# Floor_u_controller.net
KiCad netlist of a schematic drawn in Altium Designer
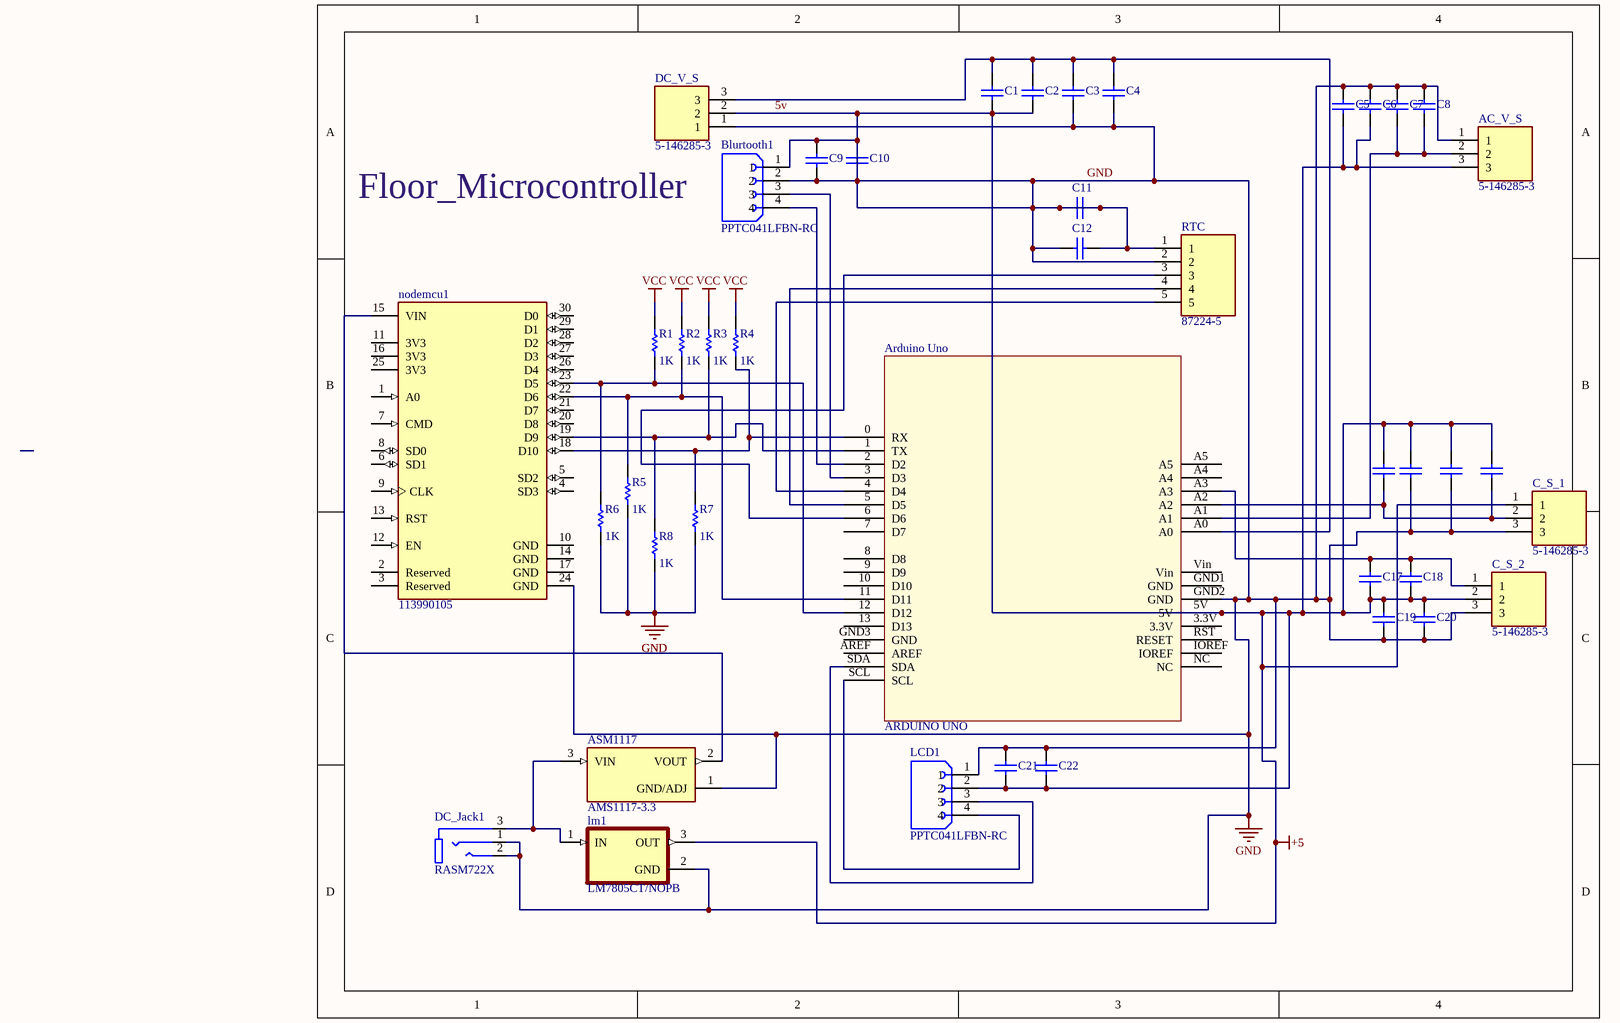
[diagram p0: Floor_u_controller.SchDoc]

(export (version "E")
  (design (tool "Eeschema 10.0.6"))
  (components
    (comp (ref "AC_V_S")
      (value "5-146285-3")
      (footprint "TE_5-146285-3:TE_5-146285-3")
      (libsource (lib "") (part "5-146285-3_1"))
    )
    (comp (ref "Arduino Uno")
      (value "ARDUINO UNO")
      (footprint "ARDUINO UNO")
      (libsource (lib "Arduino") (part "ARDUINO UNO"))
    )
    (comp (ref "ASM1117")
      (value "AMS1117-3.3")
      (footprint "SOT229P700X180-4N")
      (description "Sot223/Pkg 1-Amp 3.3-Volt Low Drop Out Voltage Regulatator")
      (fields (field (name "MF") "Advanced Monolithic Systems"))
      (libsource (lib "AMS1117-3.3") (part "AMS1117-3.3"))
    )
    (comp (ref "Blurtooth1")
      (value "PPTC041LFBN-RC")
      (footprint "SULLINS_PPTC041LFBN-RC")
      (description "4 Position Header Connector 0.100 (2.54mm) Through Hole Tin")
      (fields (field (name "MF") "Sullins Connector") (field (name "DIGI-KEY_PART_NUMBER") "S7002-ND"))
      (libsource (lib "PPTC041LFBN-RC") (part "PPTC041LFBN-RC"))
    )
    (comp (ref "C1")
      (value "~")
      (footprint "0805")
      (description "Capacitor")
      (fields (field (name "PUBLISHER") "Altium Limited"))
      (libsource (lib "Miscellaneous Devices") (part "Cap"))
    )
    (comp (ref "C2")
      (value "~")
      (footprint "0805")
      (description "Capacitor")
      (fields (field (name "PUBLISHER") "Altium Limited"))
      (libsource (lib "Miscellaneous Devices") (part "Cap"))
    )
    (comp (ref "C3")
      (value "~")
      (footprint "0805")
      (description "Capacitor")
      (fields (field (name "PUBLISHER") "Altium Limited"))
      (libsource (lib "Miscellaneous Devices") (part "Cap"))
    )
    (comp (ref "C4")
      (value "~")
      (footprint "0805")
      (description "Capacitor")
      (fields (field (name "PUBLISHER") "Altium Limited"))
      (libsource (lib "Miscellaneous Devices") (part "Cap"))
    )
    (comp (ref "C5")
      (value "~")
      (footprint "0805")
      (description "Capacitor")
      (fields (field (name "PUBLISHER") "Altium Limited"))
      (libsource (lib "Miscellaneous Devices") (part "Cap"))
    )
    (comp (ref "C6")
      (value "~")
      (footprint "0805")
      (description "Capacitor")
      (fields (field (name "PUBLISHER") "Altium Limited"))
      (libsource (lib "Miscellaneous Devices") (part "Cap"))
    )
    (comp (ref "C7")
      (value "~")
      (footprint "0805")
      (description "Capacitor")
      (fields (field (name "PUBLISHER") "Altium Limited"))
      (libsource (lib "Miscellaneous Devices") (part "Cap"))
    )
    (comp (ref "C8")
      (value "~")
      (footprint "0805")
      (description "Capacitor")
      (fields (field (name "PUBLISHER") "Altium Limited"))
      (libsource (lib "Miscellaneous Devices") (part "Cap"))
    )
    (comp (ref "C9")
      (value "~")
      (footprint "0805")
      (description "Capacitor")
      (fields (field (name "PUBLISHER") "Altium Limited"))
      (libsource (lib "Miscellaneous Devices") (part "Cap"))
    )
    (comp (ref "C10")
      (value "~")
      (footprint "0805")
      (description "Capacitor")
      (fields (field (name "PUBLISHER") "Altium Limited"))
      (libsource (lib "Miscellaneous Devices") (part "Cap"))
    )
    (comp (ref "C11")
      (value "~")
      (footprint "0805")
      (description "Capacitor")
      (fields (field (name "PUBLISHER") "Altium Limited"))
      (libsource (lib "Miscellaneous Devices") (part "Cap"))
    )
    (comp (ref "C12")
      (value "~")
      (footprint "0805")
      (description "Capacitor")
      (fields (field (name "PUBLISHER") "Altium Limited"))
      (libsource (lib "Miscellaneous Devices") (part "Cap"))
    )
    (comp (ref "C13")
      (value "~")
      (footprint "0805")
      (description "Capacitor")
      (fields (field (name "PUBLISHER") "Altium Limited"))
      (libsource (lib "Miscellaneous Devices") (part "Cap"))
    )
    (comp (ref "C14")
      (value "~")
      (footprint "0805")
      (description "Capacitor")
      (fields (field (name "PUBLISHER") "Altium Limited"))
      (libsource (lib "Miscellaneous Devices") (part "Cap"))
    )
    (comp (ref "C15")
      (value "~")
      (footprint "0805")
      (description "Capacitor")
      (fields (field (name "PUBLISHER") "Altium Limited"))
      (libsource (lib "Miscellaneous Devices") (part "Cap"))
    )
    (comp (ref "C16")
      (value "~")
      (footprint "0805")
      (description "Capacitor")
      (fields (field (name "PUBLISHER") "Altium Limited"))
      (libsource (lib "Miscellaneous Devices") (part "Cap"))
    )
    (comp (ref "C17")
      (value "~")
      (footprint "0805")
      (description "Capacitor")
      (fields (field (name "PUBLISHER") "Altium Limited"))
      (libsource (lib "Miscellaneous Devices") (part "Cap"))
    )
    (comp (ref "C18")
      (value "~")
      (footprint "0805")
      (description "Capacitor")
      (fields (field (name "PUBLISHER") "Altium Limited"))
      (libsource (lib "Miscellaneous Devices") (part "Cap"))
    )
    (comp (ref "C19")
      (value "~")
      (footprint "0805")
      (description "Capacitor")
      (fields (field (name "PUBLISHER") "Altium Limited"))
      (libsource (lib "Miscellaneous Devices") (part "Cap"))
    )
    (comp (ref "C20")
      (value "~")
      (footprint "0805")
      (description "Capacitor")
      (fields (field (name "PUBLISHER") "Altium Limited"))
      (libsource (lib "Miscellaneous Devices") (part "Cap"))
    )
    (comp (ref "C21")
      (value "~")
      (footprint "0805")
      (description "Capacitor")
      (fields (field (name "PUBLISHER") "Altium Limited"))
      (libsource (lib "Miscellaneous Devices") (part "Cap"))
    )
    (comp (ref "C22")
      (value "~")
      (footprint "0805")
      (description "Capacitor")
      (fields (field (name "PUBLISHER") "Altium Limited"))
      (libsource (lib "Miscellaneous Devices") (part "Cap"))
    )
    (comp (ref "C_S_1")
      (value "5-146285-3")
      (footprint "TE_5-146285-3:TE_5-146285-3")
      (libsource (lib "") (part "5-146285-3_1"))
    )
    (comp (ref "C_S_2")
      (value "5-146285-3")
      (footprint "TE_5-146285-3:TE_5-146285-3")
      (libsource (lib "") (part "5-146285-3_1"))
    )
    (comp (ref "DC_Jack1")
      (value "RASM722X")
      (footprint "SWITCHCRAFT_RASM722X")
      (fields (field (name "MF") "Switchcraft"))
      (libsource (lib "RASM722X") (part "RASM722X"))
    )
    (comp (ref "DC_V_S")
      (value "5-146285-3")
      (footprint "TE_5-146285-3:TE_5-146285-3")
      (libsource (lib "5-146285-3") (part "5-146285-3"))
    )
    (comp (ref "LCD1")
      (value "PPTC041LFBN-RC")
      (footprint "SULLINS_PPTC041LFBN-RC")
      (description "4 Position Header Connector 0.100 (2.54mm) Through Hole Tin")
      (fields (field (name "MF") "Sullins Connector") (field (name "DIGI-KEY_PART_NUMBER") "S7002-ND"))
      (libsource (lib "PPTC041LFBN-RC") (part "PPTC041LFBN-RC"))
    )
    (comp (ref "lm1")
      (value "LM7805CT/NOPB")
      (footprint "TO254P1054X470X2600-3")
      (description "Linear Voltage Regulator IC Positive Fixed 1 Output 1.5A TO-220-3")
      (fields (field (name "MF") "ON Semiconductor") (field (name "MP") "LM7805CT"))
      (libsource (lib "LM7805CT_NOPB") (part "LM7805CT/NOPB"))
    )
    (comp (ref "nodemcu1")
      (value "113990105")
      (footprint "FP-113990105-MFG")
      (description "NODEMCU V2 LUA BASED ESP8266 DEV")
      (libsource (lib "nodemcu") (part "CMP-138991-000001-1"))
    )
    (comp (ref "R1")
      (value "1K")
      (footprint "0805")
      (description "Resistor")
      (fields (field (name "PUBLISHER") "Altium Limited"))
      (libsource (lib "Miscellaneous Devices") (part "Res1"))
    )
    (comp (ref "R2")
      (value "1K")
      (footprint "0805")
      (description "Resistor")
      (fields (field (name "PUBLISHER") "Altium Limited"))
      (libsource (lib "Miscellaneous Devices") (part "Res1"))
    )
    (comp (ref "R3")
      (value "1K")
      (footprint "0805")
      (description "Resistor")
      (fields (field (name "PUBLISHER") "Altium Limited"))
      (libsource (lib "Miscellaneous Devices") (part "Res1"))
    )
    (comp (ref "R4")
      (value "1K")
      (footprint "0805")
      (description "Resistor")
      (fields (field (name "PUBLISHER") "Altium Limited"))
      (libsource (lib "Miscellaneous Devices") (part "Res1"))
    )
    (comp (ref "R5")
      (value "1K")
      (footprint "0805")
      (description "Resistor")
      (fields (field (name "PUBLISHER") "Altium Limited"))
      (libsource (lib "Miscellaneous Devices") (part "Res1"))
    )
    (comp (ref "R6")
      (value "1K")
      (footprint "0805")
      (description "Resistor")
      (fields (field (name "PUBLISHER") "Altium Limited"))
      (libsource (lib "Miscellaneous Devices") (part "Res1"))
    )
    (comp (ref "R7")
      (value "1K")
      (footprint "0805")
      (description "Resistor")
      (fields (field (name "PUBLISHER") "Altium Limited"))
      (libsource (lib "Miscellaneous Devices") (part "Res1"))
    )
    (comp (ref "R8")
      (value "1K")
      (footprint "0805")
      (description "Resistor")
      (fields (field (name "PUBLISHER") "Altium Limited"))
      (libsource (lib "Miscellaneous Devices") (part "Res1"))
    )
    (comp (ref "RTC")
      (value "87224-5")
      (footprint "TE_87224-5:TE_87224-5")
      (description "Conn Unshrouded Header HDR 5 POS 2.54mm Solder ST Thru-Hole")
      (fields (field (name "MF") "TE Connectivity"))
      (libsource (lib "87224-5") (part "87224-5"))
    )
  )
  (nets
    (net (code "1") (name "+5") (class "Default")
      (node (ref "AC_V_S") (pin "1") (pinfunction "1_1") (pintype "passive"))
      (node (ref "AC_V_S") (pin "3") (pinfunction "3_3") (pintype "passive"))
      (node (ref "ASM1117") (pin "1") (pinfunction "GND/ADJ_1") (pintype "power_in"))
      (node (ref "Arduino Uno") (pin "5V") (pinfunction "5V_5V") (pintype "passive"))
      (node (ref "Arduino Uno") (pin "GND2") (pinfunction "GND_GND2") (pintype "passive"))
      (node (ref "Blurtooth1") (pin "1") (pinfunction "1_1") (pintype "passive"))
      (node (ref "Blurtooth1") (pin "2") (pinfunction "2_2") (pintype "passive"))
      (node (ref "C1") (pin "1") (pinfunction "1_1") (pintype "passive"))
      (node (ref "C10") (pin "1") (pinfunction "1_1") (pintype "passive"))
      (node (ref "C10") (pin "2") (pinfunction "2_2") (pintype "passive"))
      (node (ref "C11") (pin "1") (pinfunction "1_1") (pintype "passive"))
      (node (ref "C11") (pin "2") (pinfunction "2_2") (pintype "passive"))
      (node (ref "C12") (pin "1") (pinfunction "1_1") (pintype "passive"))
      (node (ref "C12") (pin "2") (pinfunction "2_2") (pintype "passive"))
      (node (ref "C13") (pin "2") (pinfunction "2_2") (pintype "passive"))
      (node (ref "C14") (pin "1") (pinfunction "1_1") (pintype "passive"))
      (node (ref "C14") (pin "2") (pinfunction "2_2") (pintype "passive"))
      (node (ref "C15") (pin "1") (pinfunction "1_1") (pintype "passive"))
      (node (ref "C15") (pin "2") (pinfunction "2_2") (pintype "passive"))
      (node (ref "C16") (pin "2") (pinfunction "2_2") (pintype "passive"))
      (node (ref "C17") (pin "1") (pinfunction "1_1") (pintype "passive"))
      (node (ref "C18") (pin "1") (pinfunction "1_1") (pintype "passive"))
      (node (ref "C19") (pin "1") (pinfunction "1_1") (pintype "passive"))
      (node (ref "C19") (pin "2") (pinfunction "2_2") (pintype "passive"))
      (node (ref "C2") (pin "1") (pinfunction "1_1") (pintype "passive"))
      (node (ref "C20") (pin "1") (pinfunction "1_1") (pintype "passive"))
      (node (ref "C20") (pin "2") (pinfunction "2_2") (pintype "passive"))
      (node (ref "C21") (pin "1") (pinfunction "1_1") (pintype "passive"))
      (node (ref "C21") (pin "2") (pinfunction "2_2") (pintype "passive"))
      (node (ref "C22") (pin "1") (pinfunction "1_1") (pintype "passive"))
      (node (ref "C22") (pin "2") (pinfunction "2_2") (pintype "passive"))
      (node (ref "C3") (pin "1") (pinfunction "1_1") (pintype "passive"))
      (node (ref "C4") (pin "1") (pinfunction "1_1") (pintype "passive"))
      (node (ref "C5") (pin "1") (pinfunction "1_1") (pintype "passive"))
      (node (ref "C5") (pin "2") (pinfunction "2_2") (pintype "passive"))
      (node (ref "C6") (pin "1") (pinfunction "1_1") (pintype "passive"))
      (node (ref "C6") (pin "2") (pinfunction "2_2") (pintype "passive"))
      (node (ref "C7") (pin "2") (pinfunction "2_2") (pintype "passive"))
      (node (ref "C8") (pin "2") (pinfunction "2_2") (pintype "passive"))
      (node (ref "C9") (pin "1") (pinfunction "1_1") (pintype "passive"))
      (node (ref "C9") (pin "2") (pinfunction "2_2") (pintype "passive"))
      (node (ref "C_S_1") (pin "1") (pinfunction "1_1") (pintype "passive"))
      (node (ref "C_S_1") (pin "3") (pinfunction "3_3") (pintype "passive"))
      (node (ref "C_S_2") (pin "2") (pinfunction "2_2") (pintype "passive"))
      (node (ref "C_S_2") (pin "3") (pinfunction "3_3") (pintype "passive"))
      (node (ref "DC_Jack1") (pin "1") (pinfunction "SHUNT_1") (pintype "passive"))
      (node (ref "DC_Jack1") (pin "2") (pinfunction "TIP_2") (pintype "passive"))
      (node (ref "DC_V_S") (pin "1") (pinfunction "1_1") (pintype "passive"))
      (node (ref "DC_V_S") (pin "2") (pinfunction "2_2") (pintype "passive"))
      (node (ref "LCD1") (pin "1") (pinfunction "1_1") (pintype "passive"))
      (node (ref "LCD1") (pin "2") (pinfunction "2_2") (pintype "passive"))
      (node (ref "R5") (pin "1") (pinfunction "1_1") (pintype "passive"))
      (node (ref "R6") (pin "1") (pinfunction "1_1") (pintype "passive"))
      (node (ref "R7") (pin "1") (pinfunction "1_1") (pintype "passive"))
      (node (ref "R8") (pin "1") (pinfunction "1_1") (pintype "passive"))
      (node (ref "RTC") (pin "1") (pinfunction "1_1") (pintype "passive"))
      (node (ref "RTC") (pin "2") (pinfunction "2_2") (pintype "passive"))
      (node (ref "lm1") (pin "2") (pinfunction "GND_2") (pintype "power_in"))
      (node (ref "lm1") (pin "3") (pinfunction "OUT_3") (pintype "output"))
      (node (ref "nodemcu1") (pin "24") (pinfunction "GND_24") (pintype "power_in"))
    )
    (net (code "2") (name "Net-(AC_V_S-Pad2)") (class "Default")
      (node (ref "AC_V_S") (pin "2") (pinfunction "2_2") (pintype "passive"))
      (node (ref "Arduino Uno") (pin "A1") (pinfunction "A1_A1") (pintype "passive"))
      (node (ref "C7") (pin "1") (pinfunction "1_1") (pintype "passive"))
      (node (ref "C8") (pin "1") (pinfunction "1_1") (pintype "passive"))
    )
    (net (code "3") (name "Net-(ASM1117-VIN)") (class "Default")
      (node (ref "ASM1117") (pin "3") (pinfunction "VIN_3") (pintype "input"))
      (node (ref "DC_Jack1") (pin "3") (pinfunction "SLEEVE_3") (pintype "passive"))
      (node (ref "lm1") (pin "1") (pinfunction "IN_1") (pintype "input"))
    )
    (net (code "4") (name "Net-(ASM1117-VOUT)") (class "Default")
      (node (ref "ASM1117") (pin "2") (pinfunction "VOUT_2") (pintype "output"))
      (node (ref "nodemcu1") (pin "15") (pinfunction "VIN_15") (pintype "power_in"))
    )
    (net (code "5") (name "Net-(Arduino Uno-D2)") (class "Default")
      (node (ref "Arduino Uno") (pin "2") (pinfunction "D2_2") (pintype "passive"))
      (node (ref "Blurtooth1") (pin "4") (pinfunction "4_4") (pintype "passive"))
    )
    (net (code "6") (name "Net-(Arduino Uno-D3)") (class "Default")
      (node (ref "Arduino Uno") (pin "3") (pinfunction "D3_3") (pintype "passive"))
      (node (ref "Blurtooth1") (pin "3") (pinfunction "3_3") (pintype "passive"))
    )
    (net (code "7") (name "Net-(Arduino Uno-D4)") (class "Default")
      (node (ref "Arduino Uno") (pin "4") (pinfunction "D4_4") (pintype "passive"))
      (node (ref "RTC") (pin "5") (pinfunction "5_5") (pintype "passive"))
    )
    (net (code "8") (name "Net-(Arduino Uno-D5)") (class "Default")
      (node (ref "Arduino Uno") (pin "5") (pinfunction "D5_5") (pintype "passive"))
      (node (ref "RTC") (pin "4") (pinfunction "4_4") (pintype "passive"))
    )
    (net (code "9") (name "Net-(Arduino Uno-D6)") (class "Default")
      (node (ref "Arduino Uno") (pin "6") (pinfunction "D6_6") (pintype "passive"))
      (node (ref "RTC") (pin "3") (pinfunction "3_3") (pintype "passive"))
    )
    (net (code "10") (name "Net-(Arduino Uno-D11)") (class "Default")
      (node (ref "Arduino Uno") (pin "11") (pinfunction "D11_11") (pintype "passive"))
      (node (ref "R2") (pin "1") (pinfunction "1_1") (pintype "passive"))
      (node (ref "R5") (pin "2") (pinfunction "2_2") (pintype "passive"))
      (node (ref "nodemcu1") (pin "22") (pinfunction "D6_22") (pintype "bidirectional"))
    )
    (net (code "11") (name "Net-(Arduino Uno-D12)") (class "Default")
      (node (ref "Arduino Uno") (pin "12") (pinfunction "D12_12") (pintype "passive"))
      (node (ref "R1") (pin "1") (pinfunction "1_1") (pintype "passive"))
      (node (ref "R6") (pin "2") (pinfunction "2_2") (pintype "passive"))
      (node (ref "nodemcu1") (pin "23") (pinfunction "D5_23") (pintype "bidirectional"))
    )
    (net (code "12") (name "Net-(Arduino Uno-PadA0)") (class "Default")
      (node (ref "Arduino Uno") (pin "A0") (pinfunction "A0_A0") (pintype "passive"))
      (node (ref "C1") (pin "2") (pinfunction "2_2") (pintype "passive"))
      (node (ref "C2") (pin "2") (pinfunction "2_2") (pintype "passive"))
      (node (ref "C3") (pin "2") (pinfunction "2_2") (pintype "passive"))
      (node (ref "C4") (pin "2") (pinfunction "2_2") (pintype "passive"))
      (node (ref "DC_V_S") (pin "3") (pinfunction "3_3") (pintype "passive"))
    )
    (net (code "13") (name "Net-(Arduino Uno-PadA2)") (class "Default")
      (node (ref "Arduino Uno") (pin "A2") (pinfunction "A2_A2") (pintype "passive"))
      (node (ref "C13") (pin "1") (pinfunction "1_1") (pintype "passive"))
      (node (ref "C16") (pin "1") (pinfunction "1_1") (pintype "passive"))
      (node (ref "C_S_1") (pin "2") (pinfunction "2_2") (pintype "passive"))
    )
    (net (code "14") (name "Net-(Arduino Uno-PadA3)") (class "Default")
      (node (ref "Arduino Uno") (pin "A3") (pinfunction "A3_A3") (pintype "passive"))
      (node (ref "C17") (pin "2") (pinfunction "2_2") (pintype "passive"))
      (node (ref "C18") (pin "2") (pinfunction "2_2") (pintype "passive"))
      (node (ref "C_S_2") (pin "1") (pinfunction "1_1") (pintype "passive"))
    )
    (net (code "15") (name "Net-(Arduino Uno-PadSCL)") (class "Default")
      (node (ref "Arduino Uno") (pin "SCL") (pinfunction "SCL_SCL") (pintype "passive"))
      (node (ref "LCD1") (pin "4") (pinfunction "4_4") (pintype "passive"))
    )
    (net (code "16") (name "Net-(Arduino Uno-PadSDA)") (class "Default")
      (node (ref "Arduino Uno") (pin "SDA") (pinfunction "SDA_SDA") (pintype "passive"))
      (node (ref "LCD1") (pin "3") (pinfunction "3_3") (pintype "passive"))
    )
    (net (code "17") (name "Net-(Arduino Uno-RX)") (class "Default")
      (node (ref "Arduino Uno") (pin "0") (pinfunction "RX_0") (pintype "passive"))
      (node (ref "R4") (pin "1") (pinfunction "1_1") (pintype "passive"))
      (node (ref "R7") (pin "2") (pinfunction "2_2") (pintype "passive"))
      (node (ref "nodemcu1") (pin "18") (pinfunction "D10_18") (pintype "bidirectional"))
    )
    (net (code "18") (name "Net-(Arduino Uno-TX)") (class "Default")
      (node (ref "Arduino Uno") (pin "1") (pinfunction "TX_1") (pintype "passive"))
      (node (ref "R3") (pin "1") (pinfunction "1_1") (pintype "passive"))
      (node (ref "R8") (pin "2") (pinfunction "2_2") (pintype "passive"))
      (node (ref "nodemcu1") (pin "19") (pinfunction "D9_19") (pintype "bidirectional"))
    )
    (net (code "19") (name "VCC") (class "Default")
      (node (ref "R1") (pin "2") (pinfunction "2_2") (pintype "passive"))
      (node (ref "R2") (pin "2") (pinfunction "2_2") (pintype "passive"))
      (node (ref "R3") (pin "2") (pinfunction "2_2") (pintype "passive"))
      (node (ref "R4") (pin "2") (pinfunction "2_2") (pintype "passive"))
    )
    (net (code "20") (name "unconnected-(Arduino Uno-D7-Pad7)") (class "Default")
      (node (ref "Arduino Uno") (pin "7") (pinfunction "D7_7") (pintype "passive"))
    )
    (net (code "21") (name "unconnected-(Arduino Uno-D8-Pad8)") (class "Default")
      (node (ref "Arduino Uno") (pin "8") (pinfunction "D8_8") (pintype "passive"))
    )
    (net (code "22") (name "unconnected-(Arduino Uno-D9-Pad9)") (class "Default")
      (node (ref "Arduino Uno") (pin "9") (pinfunction "D9_9") (pintype "passive"))
    )
    (net (code "23") (name "unconnected-(Arduino Uno-D10-Pad10)") (class "Default")
      (node (ref "Arduino Uno") (pin "10") (pinfunction "D10_10") (pintype "passive"))
    )
    (net (code "24") (name "unconnected-(Arduino Uno-D13-Pad13)") (class "Default")
      (node (ref "Arduino Uno") (pin "13") (pinfunction "D13_13") (pintype "passive"))
    )
    (net (code "25") (name "unconnected-(Arduino Uno-GND-PadGND1)") (class "Default")
      (node (ref "Arduino Uno") (pin "GND1") (pinfunction "GND_GND1") (pintype "passive"))
    )
    (net (code "26") (name "unconnected-(Arduino Uno-GND-PadGND3)") (class "Default")
      (node (ref "Arduino Uno") (pin "GND3") (pinfunction "GND_GND3") (pintype "passive"))
    )
    (net (code "27") (name "unconnected-(Arduino Uno-Pad3.3V)") (class "Default")
      (node (ref "Arduino Uno") (pin "3.3V") (pinfunction "3.3V_3.3V") (pintype "passive"))
    )
    (net (code "28") (name "unconnected-(Arduino Uno-PadA4)") (class "Default")
      (node (ref "Arduino Uno") (pin "A4") (pinfunction "A4_A4") (pintype "passive"))
    )
    (net (code "29") (name "unconnected-(Arduino Uno-PadA5)") (class "Default")
      (node (ref "Arduino Uno") (pin "A5") (pinfunction "A5_A5") (pintype "passive"))
    )
    (net (code "30") (name "unconnected-(Arduino Uno-PadAREF)") (class "Default")
      (node (ref "Arduino Uno") (pin "AREF") (pinfunction "AREF_AREF") (pintype "passive"))
    )
    (net (code "31") (name "unconnected-(Arduino Uno-PadIOREF)") (class "Default")
      (node (ref "Arduino Uno") (pin "IOREF") (pinfunction "IOREF_IOREF") (pintype "passive"))
    )
    (net (code "32") (name "unconnected-(Arduino Uno-PadNC)") (class "Default")
      (node (ref "Arduino Uno") (pin "NC") (pinfunction "NC_NC") (pintype "passive"))
    )
    (net (code "33") (name "unconnected-(Arduino Uno-PadVin)") (class "Default")
      (node (ref "Arduino Uno") (pin "Vin") (pinfunction "Vin_Vin") (pintype "passive"))
    )
    (net (code "34") (name "unconnected-(Arduino Uno-RESET-PadRST)") (class "Default")
      (node (ref "Arduino Uno") (pin "RST") (pinfunction "RESET_RST") (pintype "passive"))
    )
    (net (code "35") (name "unconnected-(nodemcu1-3V3-Pad11)") (class "Default")
      (node (ref "nodemcu1") (pin "11") (pinfunction "3V3_11") (pintype "power_in"))
    )
    (net (code "36") (name "unconnected-(nodemcu1-3V3-Pad16)") (class "Default")
      (node (ref "nodemcu1") (pin "16") (pinfunction "3V3_16") (pintype "power_in"))
    )
    (net (code "37") (name "unconnected-(nodemcu1-3V3-Pad25)") (class "Default")
      (node (ref "nodemcu1") (pin "25") (pinfunction "3V3_25") (pintype "power_in"))
    )
    (net (code "38") (name "unconnected-(nodemcu1-A0-Pad1)") (class "Default")
      (node (ref "nodemcu1") (pin "1") (pinfunction "A0_1") (pintype "input"))
    )
    (net (code "39") (name "unconnected-(nodemcu1-CLK-Pad9)") (class "Default")
      (node (ref "nodemcu1") (pin "9") (pinfunction "CLK_9") (pintype "input"))
    )
    (net (code "40") (name "unconnected-(nodemcu1-CMD-Pad7)") (class "Default")
      (node (ref "nodemcu1") (pin "7") (pinfunction "CMD_7") (pintype "input"))
    )
    (net (code "41") (name "unconnected-(nodemcu1-D0-Pad30)") (class "Default")
      (node (ref "nodemcu1") (pin "30") (pinfunction "D0_30") (pintype "bidirectional"))
    )
    (net (code "42") (name "unconnected-(nodemcu1-D1-Pad29)") (class "Default")
      (node (ref "nodemcu1") (pin "29") (pinfunction "D1_29") (pintype "bidirectional"))
    )
    (net (code "43") (name "unconnected-(nodemcu1-D2-Pad28)") (class "Default")
      (node (ref "nodemcu1") (pin "28") (pinfunction "D2_28") (pintype "bidirectional"))
    )
    (net (code "44") (name "unconnected-(nodemcu1-D3-Pad27)") (class "Default")
      (node (ref "nodemcu1") (pin "27") (pinfunction "D3_27") (pintype "bidirectional"))
    )
    (net (code "45") (name "unconnected-(nodemcu1-D4-Pad26)") (class "Default")
      (node (ref "nodemcu1") (pin "26") (pinfunction "D4_26") (pintype "bidirectional"))
    )
    (net (code "46") (name "unconnected-(nodemcu1-D7-Pad21)") (class "Default")
      (node (ref "nodemcu1") (pin "21") (pinfunction "D7_21") (pintype "bidirectional"))
    )
    (net (code "47") (name "unconnected-(nodemcu1-D8-Pad20)") (class "Default")
      (node (ref "nodemcu1") (pin "20") (pinfunction "D8_20") (pintype "bidirectional"))
    )
    (net (code "48") (name "unconnected-(nodemcu1-EN-Pad12)") (class "Default")
      (node (ref "nodemcu1") (pin "12") (pinfunction "EN_12") (pintype "input"))
    )
    (net (code "49") (name "unconnected-(nodemcu1-GND-Pad10)") (class "Default")
      (node (ref "nodemcu1") (pin "10") (pinfunction "GND_10") (pintype "power_in"))
    )
    (net (code "50") (name "unconnected-(nodemcu1-GND-Pad14)") (class "Default")
      (node (ref "nodemcu1") (pin "14") (pinfunction "GND_14") (pintype "power_in"))
    )
    (net (code "51") (name "unconnected-(nodemcu1-GND-Pad17)") (class "Default")
      (node (ref "nodemcu1") (pin "17") (pinfunction "GND_17") (pintype "power_in"))
    )
    (net (code "52") (name "unconnected-(nodemcu1-RST-Pad13)") (class "Default")
      (node (ref "nodemcu1") (pin "13") (pinfunction "RST_13") (pintype "input"))
    )
    (net (code "53") (name "unconnected-(nodemcu1-Reserved-Pad2)") (class "Default")
      (node (ref "nodemcu1") (pin "2") (pinfunction "Reserved_2") (pintype "passive"))
    )
    (net (code "54") (name "unconnected-(nodemcu1-Reserved-Pad3)") (class "Default")
      (node (ref "nodemcu1") (pin "3") (pinfunction "Reserved_3") (pintype "passive"))
    )
    (net (code "55") (name "unconnected-(nodemcu1-SD0-Pad8)") (class "Default")
      (node (ref "nodemcu1") (pin "8") (pinfunction "SD0_8") (pintype "bidirectional"))
    )
    (net (code "56") (name "unconnected-(nodemcu1-SD1-Pad6)") (class "Default")
      (node (ref "nodemcu1") (pin "6") (pinfunction "SD1_6") (pintype "bidirectional"))
    )
    (net (code "57") (name "unconnected-(nodemcu1-SD2-Pad5)") (class "Default")
      (node (ref "nodemcu1") (pin "5") (pinfunction "SD2_5") (pintype "bidirectional"))
    )
    (net (code "58") (name "unconnected-(nodemcu1-SD3-Pad4)") (class "Default")
      (node (ref "nodemcu1") (pin "4") (pinfunction "SD3_4") (pintype "bidirectional"))
    )
  )
)
